# Sheet_X_ring.net
KiCad netlist of a schematic drawn in Altium Designer
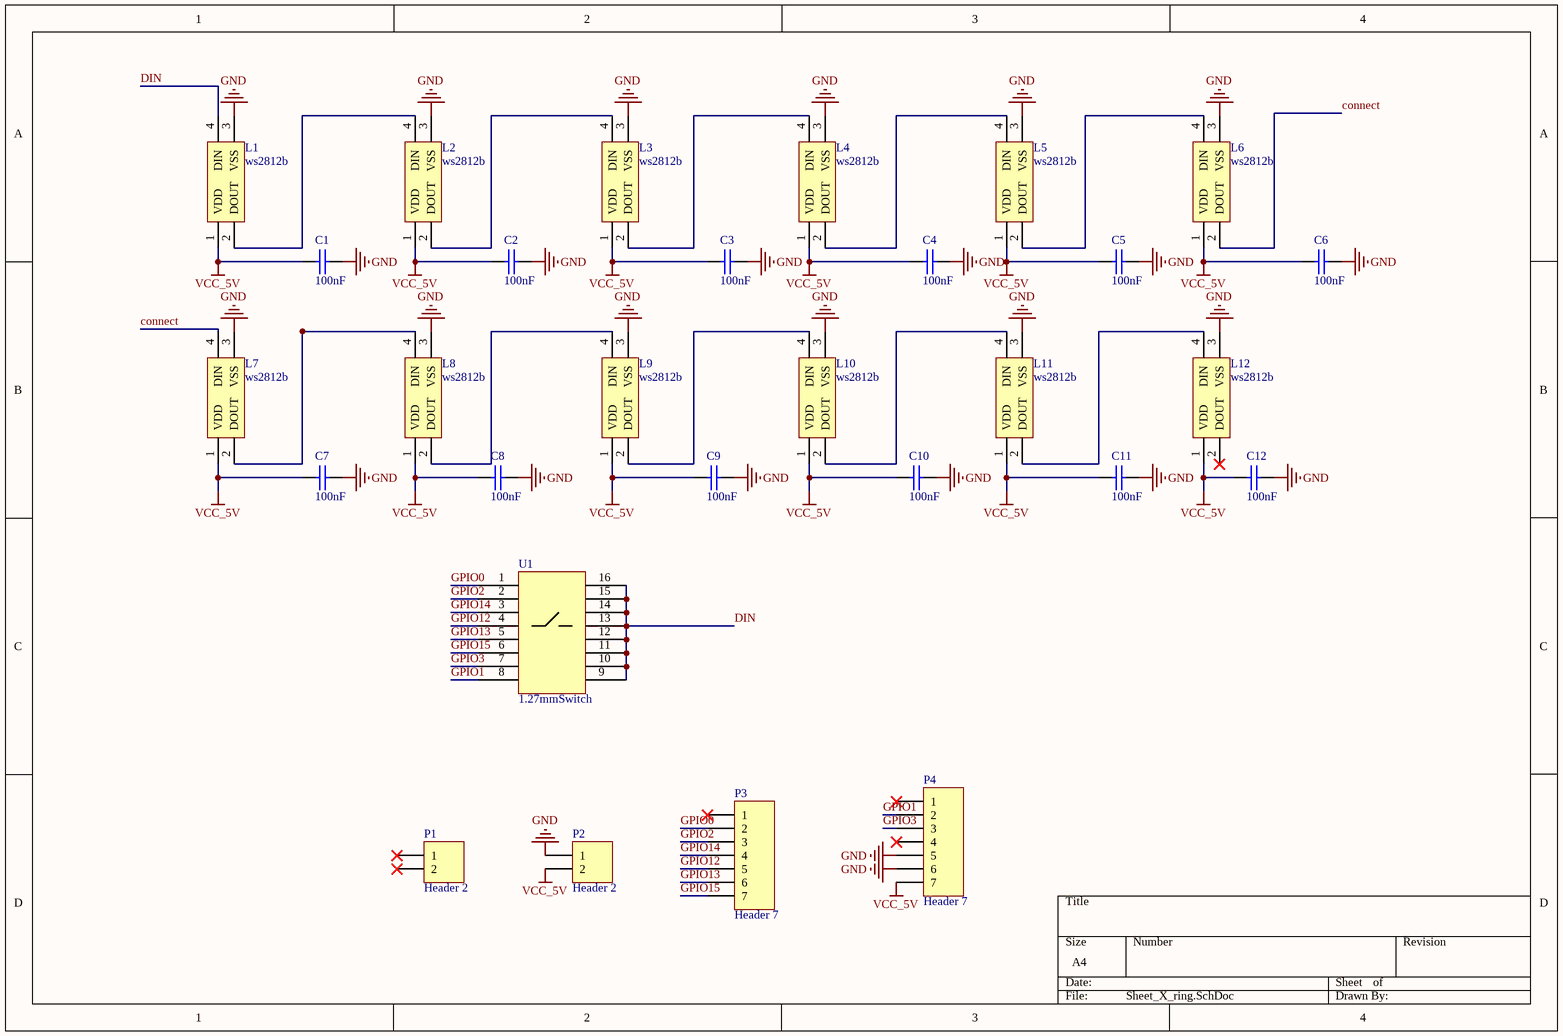
[diagram p0: Sheet_X_ring.SchDoc]

(export (version "E")
  (design (tool "Eeschema 10.0.6"))
  (components
    (comp (ref "C1")
      (value "100nF")
      (footprint "C0603")
      (description "贴片电容")
      (libsource (lib "Schlib_OLEDMCU") (part "C0603"))
    )
    (comp (ref "C2")
      (value "100nF")
      (footprint "C0603")
      (description "贴片电容")
      (libsource (lib "Schlib_OLEDMCU") (part "C0603"))
    )
    (comp (ref "C3")
      (value "100nF")
      (footprint "C0603")
      (description "贴片电容")
      (libsource (lib "Schlib_OLEDMCU") (part "C0603"))
    )
    (comp (ref "C4")
      (value "100nF")
      (footprint "C0603")
      (description "贴片电容")
      (libsource (lib "Schlib_OLEDMCU") (part "C0603"))
    )
    (comp (ref "C5")
      (value "100nF")
      (footprint "C0603")
      (description "贴片电容")
      (libsource (lib "Schlib_OLEDMCU") (part "C0603"))
    )
    (comp (ref "C6")
      (value "100nF")
      (footprint "C0603")
      (description "贴片电容")
      (libsource (lib "Schlib_OLEDMCU") (part "C0603"))
    )
    (comp (ref "C7")
      (value "100nF")
      (footprint "C0603")
      (description "贴片电容")
      (libsource (lib "Schlib_OLEDMCU") (part "C0603"))
    )
    (comp (ref "C8")
      (value "100nF")
      (footprint "C0603")
      (description "贴片电容")
      (libsource (lib "Schlib_OLEDMCU") (part "C0603"))
    )
    (comp (ref "C9")
      (value "100nF")
      (footprint "C0603")
      (description "贴片电容")
      (libsource (lib "Schlib_OLEDMCU") (part "C0603"))
    )
    (comp (ref "C10")
      (value "100nF")
      (footprint "C0603")
      (description "贴片电容")
      (libsource (lib "Schlib_OLEDMCU") (part "C0603"))
    )
    (comp (ref "C11")
      (value "100nF")
      (footprint "C0603")
      (description "贴片电容")
      (libsource (lib "Schlib_OLEDMCU") (part "C0603"))
    )
    (comp (ref "C12")
      (value "100nF")
      (footprint "C0603")
      (description "贴片电容")
      (libsource (lib "Schlib_OLEDMCU") (part "C0603"))
    )
    (comp (ref "L1")
      (value "ws2812b")
      (footprint "ws2812b")
      (description "RGB灯珠")
      (libsource (lib "Schlib_OLEDMCU") (part "ws2812b"))
    )
    (comp (ref "L2")
      (value "ws2812b")
      (footprint "ws2812b")
      (description "RGB灯珠")
      (libsource (lib "Schlib_OLEDMCU") (part "ws2812b"))
    )
    (comp (ref "L3")
      (value "ws2812b")
      (footprint "ws2812b")
      (description "RGB灯珠")
      (libsource (lib "Schlib_OLEDMCU") (part "ws2812b"))
    )
    (comp (ref "L4")
      (value "ws2812b")
      (footprint "ws2812b")
      (description "RGB灯珠")
      (libsource (lib "Schlib_OLEDMCU") (part "ws2812b"))
    )
    (comp (ref "L5")
      (value "ws2812b")
      (footprint "ws2812b")
      (description "RGB灯珠")
      (libsource (lib "Schlib_OLEDMCU") (part "ws2812b"))
    )
    (comp (ref "L6")
      (value "ws2812b")
      (footprint "ws2812b")
      (description "RGB灯珠")
      (libsource (lib "Schlib_OLEDMCU") (part "ws2812b"))
    )
    (comp (ref "L7")
      (value "ws2812b")
      (footprint "ws2812b")
      (description "RGB灯珠")
      (libsource (lib "Schlib_OLEDMCU") (part "ws2812b"))
    )
    (comp (ref "L8")
      (value "ws2812b")
      (footprint "ws2812b")
      (description "RGB灯珠")
      (libsource (lib "Schlib_OLEDMCU") (part "ws2812b"))
    )
    (comp (ref "L9")
      (value "ws2812b")
      (footprint "ws2812b")
      (description "RGB灯珠")
      (libsource (lib "Schlib_OLEDMCU") (part "ws2812b"))
    )
    (comp (ref "L10")
      (value "ws2812b")
      (footprint "ws2812b")
      (description "RGB灯珠")
      (libsource (lib "Schlib_OLEDMCU") (part "ws2812b"))
    )
    (comp (ref "L11")
      (value "ws2812b")
      (footprint "ws2812b")
      (description "RGB灯珠")
      (libsource (lib "Schlib_OLEDMCU") (part "ws2812b"))
    )
    (comp (ref "L12")
      (value "ws2812b")
      (footprint "ws2812b")
      (description "RGB灯珠")
      (libsource (lib "Schlib_OLEDMCU") (part "ws2812b"))
    )
    (comp (ref "P1")
      (value "Header 2")
      (footprint "HDR1X2")
      (description "Header, 2-Pin")
      (fields (field (name "PUBLISHER") "Altium Limited"))
      (libsource (lib "Miscellaneous Connectors") (part "Header 2"))
    )
    (comp (ref "P2")
      (value "Header 2")
      (footprint "HDR1X2")
      (description "Header, 2-Pin")
      (fields (field (name "PUBLISHER") "Altium Limited"))
      (libsource (lib "Miscellaneous Connectors") (part "Header 2"))
    )
    (comp (ref "P3")
      (value "Header 7")
      (footprint "HDR1X7")
      (description "Header, 7-Pin")
      (fields (field (name "PUBLISHER") "Altium Limited"))
      (libsource (lib "Miscellaneous Connectors") (part "Header 7"))
    )
    (comp (ref "P4")
      (value "Header 7")
      (footprint "HDR1X7")
      (description "Header, 7-Pin")
      (fields (field (name "PUBLISHER") "Altium Limited"))
      (libsource (lib "Miscellaneous Connectors") (part "Header 7"))
    )
    (comp (ref "U1")
      (value "1.27mmSwitch")
      (footprint "NumberSwitch")
      (description "拨码开关")
      (libsource (lib "Schlib_OLEDMCU") (part "NumberSwitch"))
    )
  )
  (nets
    (net (code "1") (name "/DIN") (class "Default")
      (node (ref "L1") (pin "4") (pinfunction "DIN_4") (pintype "passive"))
      (node (ref "U1") (pin "10") (pinfunction "10_10") (pintype "passive"))
      (node (ref "U1") (pin "11") (pinfunction "11_11") (pintype "passive"))
      (node (ref "U1") (pin "12") (pinfunction "12_12") (pintype "passive"))
      (node (ref "U1") (pin "13") (pinfunction "13_13") (pintype "passive"))
      (node (ref "U1") (pin "14") (pinfunction "14_14") (pintype "passive"))
      (node (ref "U1") (pin "15") (pinfunction "15_15") (pintype "passive"))
      (node (ref "U1") (pin "16") (pinfunction "16_16") (pintype "passive"))
      (node (ref "U1") (pin "9") (pinfunction "9_9") (pintype "passive"))
    )
    (net (code "2") (name "/GPIO0") (class "Default")
      (node (ref "P3") (pin "2") (pinfunction "2_2") (pintype "passive"))
      (node (ref "U1") (pin "1") (pinfunction "1_1") (pintype "passive"))
    )
    (net (code "3") (name "/GPIO1") (class "Default")
      (node (ref "P4") (pin "2") (pinfunction "2_2") (pintype "passive"))
      (node (ref "U1") (pin "8") (pinfunction "8_8") (pintype "passive"))
    )
    (net (code "4") (name "/GPIO2") (class "Default")
      (node (ref "P3") (pin "3") (pinfunction "3_3") (pintype "passive"))
      (node (ref "U1") (pin "2") (pinfunction "2_2") (pintype "passive"))
    )
    (net (code "5") (name "/GPIO3") (class "Default")
      (node (ref "P4") (pin "3") (pinfunction "3_3") (pintype "passive"))
      (node (ref "U1") (pin "7") (pinfunction "7_7") (pintype "passive"))
    )
    (net (code "6") (name "/GPIO12") (class "Default")
      (node (ref "P3") (pin "5") (pinfunction "5_5") (pintype "passive"))
      (node (ref "U1") (pin "4") (pinfunction "4_4") (pintype "passive"))
    )
    (net (code "7") (name "/GPIO13") (class "Default")
      (node (ref "P3") (pin "6") (pinfunction "6_6") (pintype "passive"))
      (node (ref "U1") (pin "5") (pinfunction "5_5") (pintype "passive"))
    )
    (net (code "8") (name "/GPIO14") (class "Default")
      (node (ref "P3") (pin "4") (pinfunction "4_4") (pintype "passive"))
      (node (ref "U1") (pin "3") (pinfunction "3_3") (pintype "passive"))
    )
    (net (code "9") (name "/GPIO15") (class "Default")
      (node (ref "P3") (pin "7") (pinfunction "7_7") (pintype "passive"))
      (node (ref "U1") (pin "6") (pinfunction "6_6") (pintype "passive"))
    )
    (net (code "10") (name "/connect") (class "Default")
      (node (ref "L6") (pin "2") (pinfunction "DOUT_2") (pintype "passive"))
      (node (ref "L7") (pin "4") (pinfunction "DIN_4") (pintype "passive"))
    )
    (net (code "11") (name "GND") (class "Default")
      (node (ref "C1") (pin "2") (pinfunction "2_2") (pintype "passive"))
      (node (ref "C10") (pin "2") (pinfunction "2_2") (pintype "passive"))
      (node (ref "C11") (pin "2") (pinfunction "2_2") (pintype "passive"))
      (node (ref "C12") (pin "2") (pinfunction "2_2") (pintype "passive"))
      (node (ref "C2") (pin "2") (pinfunction "2_2") (pintype "passive"))
      (node (ref "C3") (pin "2") (pinfunction "2_2") (pintype "passive"))
      (node (ref "C4") (pin "2") (pinfunction "2_2") (pintype "passive"))
      (node (ref "C5") (pin "2") (pinfunction "2_2") (pintype "passive"))
      (node (ref "C6") (pin "2") (pinfunction "2_2") (pintype "passive"))
      (node (ref "C7") (pin "2") (pinfunction "2_2") (pintype "passive"))
      (node (ref "C8") (pin "2") (pinfunction "2_2") (pintype "passive"))
      (node (ref "C9") (pin "2") (pinfunction "2_2") (pintype "passive"))
      (node (ref "L1") (pin "3") (pinfunction "VSS_3") (pintype "passive"))
      (node (ref "L10") (pin "3") (pinfunction "VSS_3") (pintype "passive"))
      (node (ref "L11") (pin "3") (pinfunction "VSS_3") (pintype "passive"))
      (node (ref "L12") (pin "3") (pinfunction "VSS_3") (pintype "passive"))
      (node (ref "L2") (pin "3") (pinfunction "VSS_3") (pintype "passive"))
      (node (ref "L3") (pin "3") (pinfunction "VSS_3") (pintype "passive"))
      (node (ref "L4") (pin "3") (pinfunction "VSS_3") (pintype "passive"))
      (node (ref "L5") (pin "3") (pinfunction "VSS_3") (pintype "passive"))
      (node (ref "L6") (pin "3") (pinfunction "VSS_3") (pintype "passive"))
      (node (ref "L7") (pin "3") (pinfunction "VSS_3") (pintype "passive"))
      (node (ref "L8") (pin "3") (pinfunction "VSS_3") (pintype "passive"))
      (node (ref "L9") (pin "3") (pinfunction "VSS_3") (pintype "passive"))
      (node (ref "P2") (pin "1") (pinfunction "1_1") (pintype "passive"))
      (node (ref "P4") (pin "5") (pinfunction "5_5") (pintype "passive"))
      (node (ref "P4") (pin "6") (pinfunction "6_6") (pintype "passive"))
    )
    (net (code "12") (name "Net-(L1-DOUT)") (class "Default")
      (node (ref "L1") (pin "2") (pinfunction "DOUT_2") (pintype "passive"))
      (node (ref "L2") (pin "4") (pinfunction "DIN_4") (pintype "passive"))
    )
    (net (code "13") (name "Net-(L2-DOUT)") (class "Default")
      (node (ref "L2") (pin "2") (pinfunction "DOUT_2") (pintype "passive"))
      (node (ref "L3") (pin "4") (pinfunction "DIN_4") (pintype "passive"))
    )
    (net (code "14") (name "Net-(L3-DOUT)") (class "Default")
      (node (ref "L3") (pin "2") (pinfunction "DOUT_2") (pintype "passive"))
      (node (ref "L4") (pin "4") (pinfunction "DIN_4") (pintype "passive"))
    )
    (net (code "15") (name "Net-(L4-DOUT)") (class "Default")
      (node (ref "L4") (pin "2") (pinfunction "DOUT_2") (pintype "passive"))
      (node (ref "L5") (pin "4") (pinfunction "DIN_4") (pintype "passive"))
    )
    (net (code "16") (name "Net-(L5-DOUT)") (class "Default")
      (node (ref "L5") (pin "2") (pinfunction "DOUT_2") (pintype "passive"))
      (node (ref "L6") (pin "4") (pinfunction "DIN_4") (pintype "passive"))
    )
    (net (code "17") (name "Net-(L7-DOUT)") (class "Default")
      (node (ref "L7") (pin "2") (pinfunction "DOUT_2") (pintype "passive"))
      (node (ref "L8") (pin "4") (pinfunction "DIN_4") (pintype "passive"))
    )
    (net (code "18") (name "Net-(L8-DOUT)") (class "Default")
      (node (ref "L8") (pin "2") (pinfunction "DOUT_2") (pintype "passive"))
      (node (ref "L9") (pin "4") (pinfunction "DIN_4") (pintype "passive"))
    )
    (net (code "19") (name "Net-(L10-DIN)") (class "Default")
      (node (ref "L10") (pin "4") (pinfunction "DIN_4") (pintype "passive"))
      (node (ref "L9") (pin "2") (pinfunction "DOUT_2") (pintype "passive"))
    )
    (net (code "20") (name "Net-(L10-DOUT)") (class "Default")
      (node (ref "L10") (pin "2") (pinfunction "DOUT_2") (pintype "passive"))
      (node (ref "L11") (pin "4") (pinfunction "DIN_4") (pintype "passive"))
    )
    (net (code "21") (name "Net-(L11-DOUT)") (class "Default")
      (node (ref "L11") (pin "2") (pinfunction "DOUT_2") (pintype "passive"))
      (node (ref "L12") (pin "4") (pinfunction "DIN_4") (pintype "passive"))
    )
    (net (code "22") (name "VCC_5V") (class "Default")
      (node (ref "C1") (pin "1") (pinfunction "1_1") (pintype "passive"))
      (node (ref "C10") (pin "1") (pinfunction "1_1") (pintype "passive"))
      (node (ref "C11") (pin "1") (pinfunction "1_1") (pintype "passive"))
      (node (ref "C12") (pin "1") (pinfunction "1_1") (pintype "passive"))
      (node (ref "C2") (pin "1") (pinfunction "1_1") (pintype "passive"))
      (node (ref "C3") (pin "1") (pinfunction "1_1") (pintype "passive"))
      (node (ref "C4") (pin "1") (pinfunction "1_1") (pintype "passive"))
      (node (ref "C5") (pin "1") (pinfunction "1_1") (pintype "passive"))
      (node (ref "C6") (pin "1") (pinfunction "1_1") (pintype "passive"))
      (node (ref "C7") (pin "1") (pinfunction "1_1") (pintype "passive"))
      (node (ref "C8") (pin "1") (pinfunction "1_1") (pintype "passive"))
      (node (ref "C9") (pin "1") (pinfunction "1_1") (pintype "passive"))
      (node (ref "L1") (pin "1") (pinfunction "VDD_1") (pintype "passive"))
      (node (ref "L10") (pin "1") (pinfunction "VDD_1") (pintype "passive"))
      (node (ref "L11") (pin "1") (pinfunction "VDD_1") (pintype "passive"))
      (node (ref "L12") (pin "1") (pinfunction "VDD_1") (pintype "passive"))
      (node (ref "L2") (pin "1") (pinfunction "VDD_1") (pintype "passive"))
      (node (ref "L3") (pin "1") (pinfunction "VDD_1") (pintype "passive"))
      (node (ref "L4") (pin "1") (pinfunction "VDD_1") (pintype "passive"))
      (node (ref "L5") (pin "1") (pinfunction "VDD_1") (pintype "passive"))
      (node (ref "L6") (pin "1") (pinfunction "VDD_1") (pintype "passive"))
      (node (ref "L7") (pin "1") (pinfunction "VDD_1") (pintype "passive"))
      (node (ref "L8") (pin "1") (pinfunction "VDD_1") (pintype "passive"))
      (node (ref "L9") (pin "1") (pinfunction "VDD_1") (pintype "passive"))
      (node (ref "P2") (pin "2") (pinfunction "2_2") (pintype "passive"))
      (node (ref "P4") (pin "7") (pinfunction "7_7") (pintype "passive"))
    )
    (net (code "23") (name "unconnected-(L12-DOUT-Pad2)") (class "Default")
      (node (ref "L12") (pin "2") (pinfunction "DOUT_2") (pintype "passive+no_connect"))
    )
    (net (code "24") (name "unconnected-(P1-Pad1)") (class "Default")
      (node (ref "P1") (pin "1") (pinfunction "1_1") (pintype "passive+no_connect"))
    )
    (net (code "25") (name "unconnected-(P1-Pad2)") (class "Default")
      (node (ref "P1") (pin "2") (pinfunction "2_2") (pintype "passive+no_connect"))
    )
    (net (code "26") (name "unconnected-(P3-Pad1)") (class "Default")
      (node (ref "P3") (pin "1") (pinfunction "1_1") (pintype "passive+no_connect"))
    )
    (net (code "27") (name "unconnected-(P4-Pad1)") (class "Default")
      (node (ref "P4") (pin "1") (pinfunction "1_1") (pintype "passive+no_connect"))
    )
    (net (code "28") (name "unconnected-(P4-Pad4)") (class "Default")
      (node (ref "P4") (pin "4") (pinfunction "4_4") (pintype "passive+no_connect"))
    )
  )
)
